# stm32f103c8_jlinkob_v2.net
KiCad netlist of a schematic drawn in EAGLE
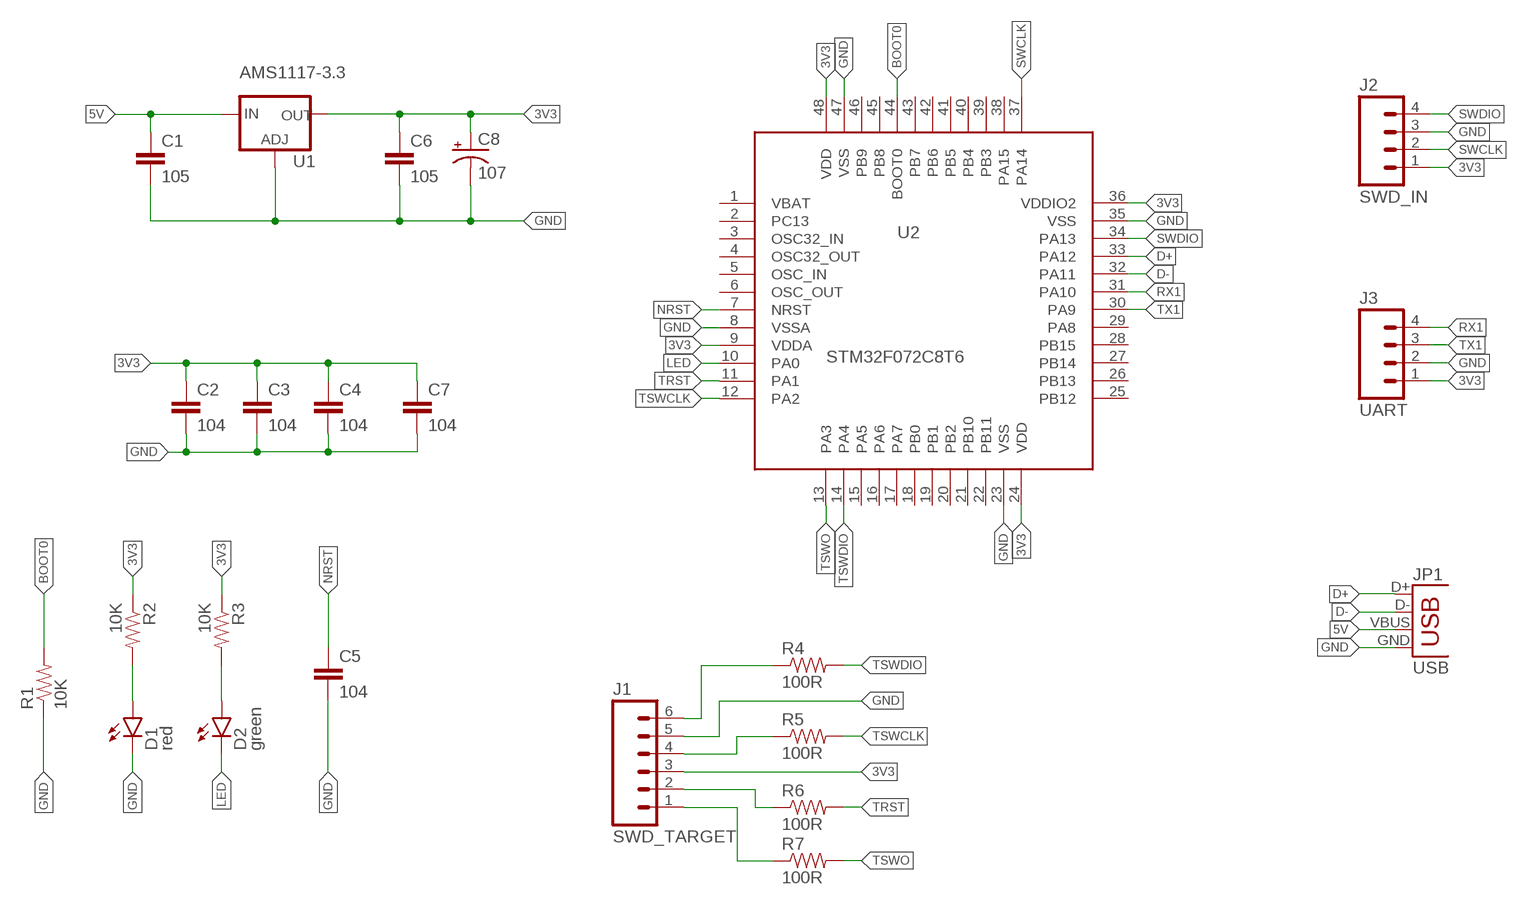
[diagram p0: schematic, sheet 1]

(export (version "E")
  (design (tool "Eeschema 10.0.6"))
  (components
    (comp (ref "C1")
      (value "105")
      (footprint "eagle-import:0603-CAP")
      (libsource (lib "eagle-import") (part "CAP0603-CAP"))
    )
    (comp (ref "C2")
      (value "104")
      (footprint "eagle-import:0603-CAP")
      (libsource (lib "eagle-import") (part "CAP0603-CAP"))
    )
    (comp (ref "C3")
      (value "104")
      (footprint "eagle-import:0603-CAP")
      (libsource (lib "eagle-import") (part "CAP0603-CAP"))
    )
    (comp (ref "C4")
      (value "104")
      (footprint "eagle-import:0603-CAP")
      (libsource (lib "eagle-import") (part "CAP0603-CAP"))
    )
    (comp (ref "C5")
      (value "104")
      (footprint "eagle-import:0603-CAP")
      (libsource (lib "eagle-import") (part "CAP0603-CAP"))
    )
    (comp (ref "C6")
      (value "105")
      (footprint "eagle-import:0603-CAP")
      (libsource (lib "eagle-import") (part "CAP0603-CAP"))
    )
    (comp (ref "C7")
      (value "104")
      (footprint "eagle-import:0603-CAP")
      (libsource (lib "eagle-import") (part "CAP0603-CAP"))
    )
    (comp (ref "C8")
      (value "107")
      (footprint "eagle-import:EIA3528")
      (libsource (lib "eagle-import") (part "CAP_POL3528"))
    )
    (comp (ref "D1")
      (value "red")
      (footprint "eagle-import:LED-0603-SEEED")
      (libsource (lib "eagle-import") (part "LED-SEEED-0603"))
    )
    (comp (ref "D2")
      (value "green")
      (footprint "eagle-import:LED-0603-SEEED")
      (libsource (lib "eagle-import") (part "LED-SEEED-0603"))
    )
    (comp (ref "J1")
      (value "SWD_TARGET")
      (footprint "eagle-import:1X06_NO_SILK")
      (libsource (lib "eagle-import") (part "M06NO_SILK_FEMALE_PTH"))
    )
    (comp (ref "J2")
      (value "SWD_IN")
      (footprint "eagle-import:1X04_NO_SILK")
      (libsource (lib "eagle-import") (part "M041X04_NO_SILK"))
    )
    (comp (ref "J3")
      (value "UART")
      (footprint "eagle-import:1X04_NO_SILK")
      (libsource (lib "eagle-import") (part "M041X04_NO_SILK"))
    )
    (comp (ref "JP1")
      (value "USB")
      (footprint "eagle-import:MICROUSB-U-F-M5DD-Y-1")
      (libsource (lib "eagle-import") (part "USB"))
    )
    (comp (ref "R1")
      (value "10K")
      (footprint "eagle-import:0603-RES")
      (libsource (lib "eagle-import") (part "RESISTOR0603"))
    )
    (comp (ref "R2")
      (value "10K")
      (footprint "eagle-import:0603-RES")
      (libsource (lib "eagle-import") (part "RESISTOR0603"))
    )
    (comp (ref "R3")
      (value "10K")
      (footprint "eagle-import:0603-RES")
      (libsource (lib "eagle-import") (part "RESISTOR0603"))
    )
    (comp (ref "R4")
      (value "100R")
      (footprint "eagle-import:0603-RES")
      (libsource (lib "eagle-import") (part "RESISTOR0603"))
    )
    (comp (ref "R5")
      (value "100R")
      (footprint "eagle-import:0603-RES")
      (libsource (lib "eagle-import") (part "RESISTOR0603"))
    )
    (comp (ref "R6")
      (value "100R")
      (footprint "eagle-import:0603-RES")
      (libsource (lib "eagle-import") (part "RESISTOR0603"))
    )
    (comp (ref "R7")
      (value "100R")
      (footprint "eagle-import:0603-RES")
      (libsource (lib "eagle-import") (part "RESISTOR0603"))
    )
    (comp (ref "U1")
      (value "AMS1117-3.3")
      (footprint "eagle-import:SOT223")
      (libsource (lib "eagle-import") (part "AMS1117SOT223"))
    )
    (comp (ref "U2")
      (value "STM32F072C8T6")
      (footprint "eagle-import:LQFP-48")
      (libsource (lib "eagle-import") (part "STM32F072C8T6"))
    )
  )
  (nets
    (net (code "1") (name "3V3") (class "Default")
      (node (ref "C2") (pin "1") (pinfunction "1_1") (pintype "passive"))
      (node (ref "C3") (pin "1") (pinfunction "1_1") (pintype "passive"))
      (node (ref "C4") (pin "1") (pinfunction "1_1") (pintype "passive"))
      (node (ref "C6") (pin "1") (pinfunction "1_1") (pintype "passive"))
      (node (ref "C7") (pin "1") (pinfunction "1_1") (pintype "passive"))
      (node (ref "C8") (pin "A") (pinfunction "+_A") (pintype "passive"))
      (node (ref "J1") (pin "3") (pinfunction "3_3") (pintype "passive"))
      (node (ref "J2") (pin "1") (pinfunction "1_1") (pintype "passive"))
      (node (ref "J3") (pin "1") (pinfunction "1_1") (pintype "passive"))
      (node (ref "R2") (pin "1") (pinfunction "1_1") (pintype "passive"))
      (node (ref "R3") (pin "1") (pinfunction "1_1") (pintype "passive"))
      (node (ref "U1") (pin "2") (pinfunction "OUT_2") (pintype "output"))
      (node (ref "U1") (pin "4") (pinfunction "OUT_4") (pintype "output"))
      (node (ref "U2") (pin "24") (pinfunction "VDD_24") (pintype "bidirectional"))
      (node (ref "U2") (pin "36") (pinfunction "VDDIO2_36") (pintype "bidirectional"))
      (node (ref "U2") (pin "48") (pinfunction "VDD_48") (pintype "bidirectional"))
      (node (ref "U2") (pin "9") (pinfunction "VDDA_9") (pintype "bidirectional"))
    )
    (net (code "2") (name "5V") (class "Default")
      (node (ref "C1") (pin "1") (pinfunction "1_1") (pintype "passive"))
      (node (ref "JP1") (pin "VBUS") (pinfunction "VBUS_VBUS") (pintype "bidirectional"))
      (node (ref "U1") (pin "3") (pinfunction "IN_3") (pintype "input"))
    )
    (net (code "3") (name "BOOT0") (class "Default")
      (node (ref "R1") (pin "2") (pinfunction "2_2") (pintype "passive"))
      (node (ref "U2") (pin "44") (pinfunction "BOOT0_44") (pintype "bidirectional"))
    )
    (net (code "4") (name "D+") (class "Default")
      (node (ref "JP1") (pin "D+") (pinfunction "D+_D+") (pintype "bidirectional"))
      (node (ref "U2") (pin "33") (pinfunction "PA12_33") (pintype "bidirectional"))
    )
    (net (code "5") (name "D-") (class "Default")
      (node (ref "JP1") (pin "D-") (pinfunction "D-_D-") (pintype "bidirectional"))
      (node (ref "U2") (pin "32") (pinfunction "PA11_32") (pintype "bidirectional"))
    )
    (net (code "6") (name "GND") (class "Default")
      (node (ref "C1") (pin "2") (pinfunction "2_2") (pintype "passive"))
      (node (ref "C2") (pin "2") (pinfunction "2_2") (pintype "passive"))
      (node (ref "C3") (pin "2") (pinfunction "2_2") (pintype "passive"))
      (node (ref "C4") (pin "2") (pinfunction "2_2") (pintype "passive"))
      (node (ref "C5") (pin "2") (pinfunction "2_2") (pintype "passive"))
      (node (ref "C6") (pin "2") (pinfunction "2_2") (pintype "passive"))
      (node (ref "C7") (pin "2") (pinfunction "2_2") (pintype "passive"))
      (node (ref "C8") (pin "C") (pinfunction "-_C") (pintype "passive"))
      (node (ref "D1") (pin "-") (pinfunction "C_-") (pintype "passive"))
      (node (ref "J1") (pin "5") (pinfunction "5_5") (pintype "passive"))
      (node (ref "J2") (pin "3") (pinfunction "3_3") (pintype "passive"))
      (node (ref "J3") (pin "2") (pinfunction "2_2") (pintype "passive"))
      (node (ref "JP1") (pin "GND") (pinfunction "GND_GND") (pintype "bidirectional"))
      (node (ref "R1") (pin "1") (pinfunction "1_1") (pintype "passive"))
      (node (ref "U1") (pin "1") (pinfunction "ADJ_1") (pintype "input"))
      (node (ref "U2") (pin "23") (pinfunction "VSS_23") (pintype "bidirectional"))
      (node (ref "U2") (pin "35") (pinfunction "VSS_35") (pintype "bidirectional"))
      (node (ref "U2") (pin "47") (pinfunction "VSS_47") (pintype "bidirectional"))
      (node (ref "U2") (pin "8") (pinfunction "VSSA_8") (pintype "bidirectional"))
    )
    (net (code "7") (name "LED") (class "Default")
      (node (ref "D2") (pin "-") (pinfunction "C_-") (pintype "passive"))
      (node (ref "U2") (pin "10") (pinfunction "PA0_10") (pintype "bidirectional"))
    )
    (net (code "8") (name "NRST") (class "Default")
      (node (ref "C5") (pin "1") (pinfunction "1_1") (pintype "passive"))
      (node (ref "U2") (pin "7") (pinfunction "NRST_7") (pintype "bidirectional"))
    )
    (net (code "9") (name "Net-(D1-A)") (class "Default")
      (node (ref "D1") (pin "+") (pinfunction "A_+") (pintype "passive"))
      (node (ref "R2") (pin "2") (pinfunction "2_2") (pintype "passive"))
    )
    (net (code "10") (name "Net-(D2-A)") (class "Default")
      (node (ref "D2") (pin "+") (pinfunction "A_+") (pintype "passive"))
      (node (ref "R3") (pin "2") (pinfunction "2_2") (pintype "passive"))
    )
    (net (code "11") (name "Net-(J1-Pad1)") (class "Default")
      (node (ref "J1") (pin "1") (pinfunction "1_1") (pintype "passive"))
      (node (ref "R7") (pin "1") (pinfunction "1_1") (pintype "passive"))
    )
    (net (code "12") (name "Net-(J1-Pad2)") (class "Default")
      (node (ref "J1") (pin "2") (pinfunction "2_2") (pintype "passive"))
      (node (ref "R6") (pin "1") (pinfunction "1_1") (pintype "passive"))
    )
    (net (code "13") (name "Net-(J1-Pad4)") (class "Default")
      (node (ref "J1") (pin "4") (pinfunction "4_4") (pintype "passive"))
      (node (ref "R5") (pin "1") (pinfunction "1_1") (pintype "passive"))
    )
    (net (code "14") (name "Net-(J1-Pad6)") (class "Default")
      (node (ref "J1") (pin "6") (pinfunction "6_6") (pintype "passive"))
      (node (ref "R4") (pin "1") (pinfunction "1_1") (pintype "passive"))
    )
    (net (code "15") (name "RX1") (class "Default")
      (node (ref "J3") (pin "4") (pinfunction "4_4") (pintype "passive"))
      (node (ref "U2") (pin "31") (pinfunction "PA10_31") (pintype "bidirectional"))
    )
    (net (code "16") (name "SWCLK") (class "Default")
      (node (ref "J2") (pin "2") (pinfunction "2_2") (pintype "passive"))
      (node (ref "U2") (pin "37") (pinfunction "PA14_37") (pintype "bidirectional"))
    )
    (net (code "17") (name "SWDIO") (class "Default")
      (node (ref "J2") (pin "4") (pinfunction "4_4") (pintype "passive"))
      (node (ref "U2") (pin "34") (pinfunction "PA13_34") (pintype "bidirectional"))
    )
    (net (code "18") (name "TRST") (class "Default")
      (node (ref "R6") (pin "2") (pinfunction "2_2") (pintype "passive"))
      (node (ref "U2") (pin "11") (pinfunction "PA1_11") (pintype "bidirectional"))
    )
    (net (code "19") (name "TSWCLK") (class "Default")
      (node (ref "R5") (pin "2") (pinfunction "2_2") (pintype "passive"))
      (node (ref "U2") (pin "12") (pinfunction "PA2_12") (pintype "bidirectional"))
    )
    (net (code "20") (name "TSWDIO") (class "Default")
      (node (ref "R4") (pin "2") (pinfunction "2_2") (pintype "passive"))
      (node (ref "U2") (pin "14") (pinfunction "PA4_14") (pintype "bidirectional"))
    )
    (net (code "21") (name "TSWO") (class "Default")
      (node (ref "R7") (pin "2") (pinfunction "2_2") (pintype "passive"))
      (node (ref "U2") (pin "13") (pinfunction "PA3_13") (pintype "bidirectional"))
    )
    (net (code "22") (name "TX1") (class "Default")
      (node (ref "J3") (pin "3") (pinfunction "3_3") (pintype "passive"))
      (node (ref "U2") (pin "30") (pinfunction "PA9_30") (pintype "bidirectional"))
    )
    (net (code "23") (name "unconnected-(U2-OSC32_IN-Pad3)") (class "Default")
      (node (ref "U2") (pin "3") (pinfunction "OSC32_IN_3") (pintype "bidirectional"))
    )
    (net (code "24") (name "unconnected-(U2-OSC32_OUT-Pad4)") (class "Default")
      (node (ref "U2") (pin "4") (pinfunction "OSC32_OUT_4") (pintype "bidirectional"))
    )
    (net (code "25") (name "unconnected-(U2-OSC_IN-Pad5)") (class "Default")
      (node (ref "U2") (pin "5") (pinfunction "OSC_IN_5") (pintype "bidirectional"))
    )
    (net (code "26") (name "unconnected-(U2-OSC_OUT-Pad6)") (class "Default")
      (node (ref "U2") (pin "6") (pinfunction "OSC_OUT_6") (pintype "bidirectional"))
    )
    (net (code "27") (name "unconnected-(U2-PA5-Pad15)") (class "Default")
      (node (ref "U2") (pin "15") (pinfunction "PA5_15") (pintype "bidirectional"))
    )
    (net (code "28") (name "unconnected-(U2-PA6-Pad16)") (class "Default")
      (node (ref "U2") (pin "16") (pinfunction "PA6_16") (pintype "bidirectional"))
    )
    (net (code "29") (name "unconnected-(U2-PA7-Pad17)") (class "Default")
      (node (ref "U2") (pin "17") (pinfunction "PA7_17") (pintype "bidirectional"))
    )
    (net (code "30") (name "unconnected-(U2-PA8-Pad29)") (class "Default")
      (node (ref "U2") (pin "29") (pinfunction "PA8_29") (pintype "bidirectional"))
    )
    (net (code "31") (name "unconnected-(U2-PA15-Pad38)") (class "Default")
      (node (ref "U2") (pin "38") (pinfunction "PA15_38") (pintype "bidirectional"))
    )
    (net (code "32") (name "unconnected-(U2-PB0-Pad18)") (class "Default")
      (node (ref "U2") (pin "18") (pinfunction "PB0_18") (pintype "bidirectional"))
    )
    (net (code "33") (name "unconnected-(U2-PB1-Pad19)") (class "Default")
      (node (ref "U2") (pin "19") (pinfunction "PB1_19") (pintype "bidirectional"))
    )
    (net (code "34") (name "unconnected-(U2-PB2-Pad20)") (class "Default")
      (node (ref "U2") (pin "20") (pinfunction "PB2_20") (pintype "bidirectional"))
    )
    (net (code "35") (name "unconnected-(U2-PB3-Pad39)") (class "Default")
      (node (ref "U2") (pin "39") (pinfunction "PB3_39") (pintype "bidirectional"))
    )
    (net (code "36") (name "unconnected-(U2-PB4-Pad40)") (class "Default")
      (node (ref "U2") (pin "40") (pinfunction "PB4_40") (pintype "bidirectional"))
    )
    (net (code "37") (name "unconnected-(U2-PB5-Pad41)") (class "Default")
      (node (ref "U2") (pin "41") (pinfunction "PB5_41") (pintype "bidirectional"))
    )
    (net (code "38") (name "unconnected-(U2-PB6-Pad42)") (class "Default")
      (node (ref "U2") (pin "42") (pinfunction "PB6_42") (pintype "bidirectional"))
    )
    (net (code "39") (name "unconnected-(U2-PB7-Pad43)") (class "Default")
      (node (ref "U2") (pin "43") (pinfunction "PB7_43") (pintype "bidirectional"))
    )
    (net (code "40") (name "unconnected-(U2-PB8-Pad45)") (class "Default")
      (node (ref "U2") (pin "45") (pinfunction "PB8_45") (pintype "bidirectional"))
    )
    (net (code "41") (name "unconnected-(U2-PB9-Pad46)") (class "Default")
      (node (ref "U2") (pin "46") (pinfunction "PB9_46") (pintype "bidirectional"))
    )
    (net (code "42") (name "unconnected-(U2-PB10-Pad21)") (class "Default")
      (node (ref "U2") (pin "21") (pinfunction "PB10_21") (pintype "bidirectional"))
    )
    (net (code "43") (name "unconnected-(U2-PB11-Pad22)") (class "Default")
      (node (ref "U2") (pin "22") (pinfunction "PB11_22") (pintype "bidirectional"))
    )
    (net (code "44") (name "unconnected-(U2-PB12-Pad25)") (class "Default")
      (node (ref "U2") (pin "25") (pinfunction "PB12_25") (pintype "bidirectional"))
    )
    (net (code "45") (name "unconnected-(U2-PB13-Pad26)") (class "Default")
      (node (ref "U2") (pin "26") (pinfunction "PB13_26") (pintype "bidirectional"))
    )
    (net (code "46") (name "unconnected-(U2-PB14-Pad27)") (class "Default")
      (node (ref "U2") (pin "27") (pinfunction "PB14_27") (pintype "bidirectional"))
    )
    (net (code "47") (name "unconnected-(U2-PB15-Pad28)") (class "Default")
      (node (ref "U2") (pin "28") (pinfunction "PB15_28") (pintype "bidirectional"))
    )
    (net (code "48") (name "unconnected-(U2-PC13-Pad2)") (class "Default")
      (node (ref "U2") (pin "2") (pinfunction "PC13_2") (pintype "bidirectional"))
    )
    (net (code "49") (name "unconnected-(U2-VBAT-Pad1)") (class "Default")
      (node (ref "U2") (pin "1") (pinfunction "VBAT_1") (pintype "bidirectional"))
    )
  )
)
